# spiEeprom.net
KiCad netlist of a schematic drawn in EAGLE
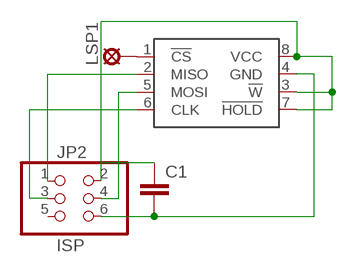
[diagram p0: schematic, sheet 1]

(export (version "E")
  (design (tool "Eeschema 10.0.6"))
  (components
    (comp (ref "C1")
      (value "C-EUC0603")
      (footprint "eagle-import:C0603")
      (libsource (lib "eagle-import") (part "C-EUC0603"))
    )
    (comp (ref "JP2")
      (value "ISP")
      (footprint "eagle-import:2X03")
      (libsource (lib "eagle-import") (part "PINHD-2X3"))
    )
    (comp (ref "LSP1")
      (value "LSP10")
      (footprint "eagle-import:LSP10")
      (libsource (lib "eagle-import") (part "LSP10"))
    )
    (comp (ref "U$1")
      (value "M95XXSO")
      (footprint "eagle-import:SO08")
      (libsource (lib "eagle-import") (part "M95XXSO"))
    )
  )
  (nets
    (net (code "1") (name "Net-(U$1-CLK)") (class "Default")
      (node (ref "JP2") (pin "3") (pinfunction "3_3") (pintype "passive"))
      (node (ref "U$1") (pin "6") (pinfunction "CLK_6") (pintype "bidirectional"))
    )
    (net (code "2") (name "Net-(U$1-GND)") (class "Default")
      (node (ref "C1") (pin "2") (pinfunction "2_2") (pintype "passive"))
      (node (ref "JP2") (pin "6") (pinfunction "6_6") (pintype "passive"))
      (node (ref "U$1") (pin "4") (pinfunction "GND_4") (pintype "bidirectional"))
    )
    (net (code "3") (name "Net-(U$1-MISO)") (class "Default")
      (node (ref "JP2") (pin "1") (pinfunction "1_1") (pintype "passive"))
      (node (ref "U$1") (pin "2") (pinfunction "MISO_2") (pintype "bidirectional"))
    )
    (net (code "4") (name "Net-(U$1-MOSI)") (class "Default")
      (node (ref "JP2") (pin "4") (pinfunction "4_4") (pintype "passive"))
      (node (ref "U$1") (pin "5") (pinfunction "MOSI_5") (pintype "bidirectional"))
    )
    (net (code "5") (name "Net-(U$1-VCC)") (class "Default")
      (node (ref "C1") (pin "1") (pinfunction "1_1") (pintype "passive"))
      (node (ref "JP2") (pin "2") (pinfunction "2_2") (pintype "passive"))
      (node (ref "U$1") (pin "3") (pinfunction "~{W}_3") (pintype "bidirectional"))
      (node (ref "U$1") (pin "7") (pinfunction "~{HOLD}_7") (pintype "bidirectional"))
      (node (ref "U$1") (pin "8") (pinfunction "VCC_8") (pintype "bidirectional"))
    )
    (net (code "6") (name "Net-(U$1-~{CS})") (class "Default")
      (node (ref "LSP1") (pin "MP") (pinfunction "MP_MP") (pintype "passive"))
      (node (ref "U$1") (pin "1") (pinfunction "~{CS}_1") (pintype "bidirectional"))
    )
    (net (code "7") (name "unconnected-(JP2-Pad5)") (class "Default")
      (node (ref "JP2") (pin "5") (pinfunction "5_5") (pintype "passive"))
    )
  )
)
